# schematic_v2.net
KiCad netlist of a schematic drawn in EAGLE
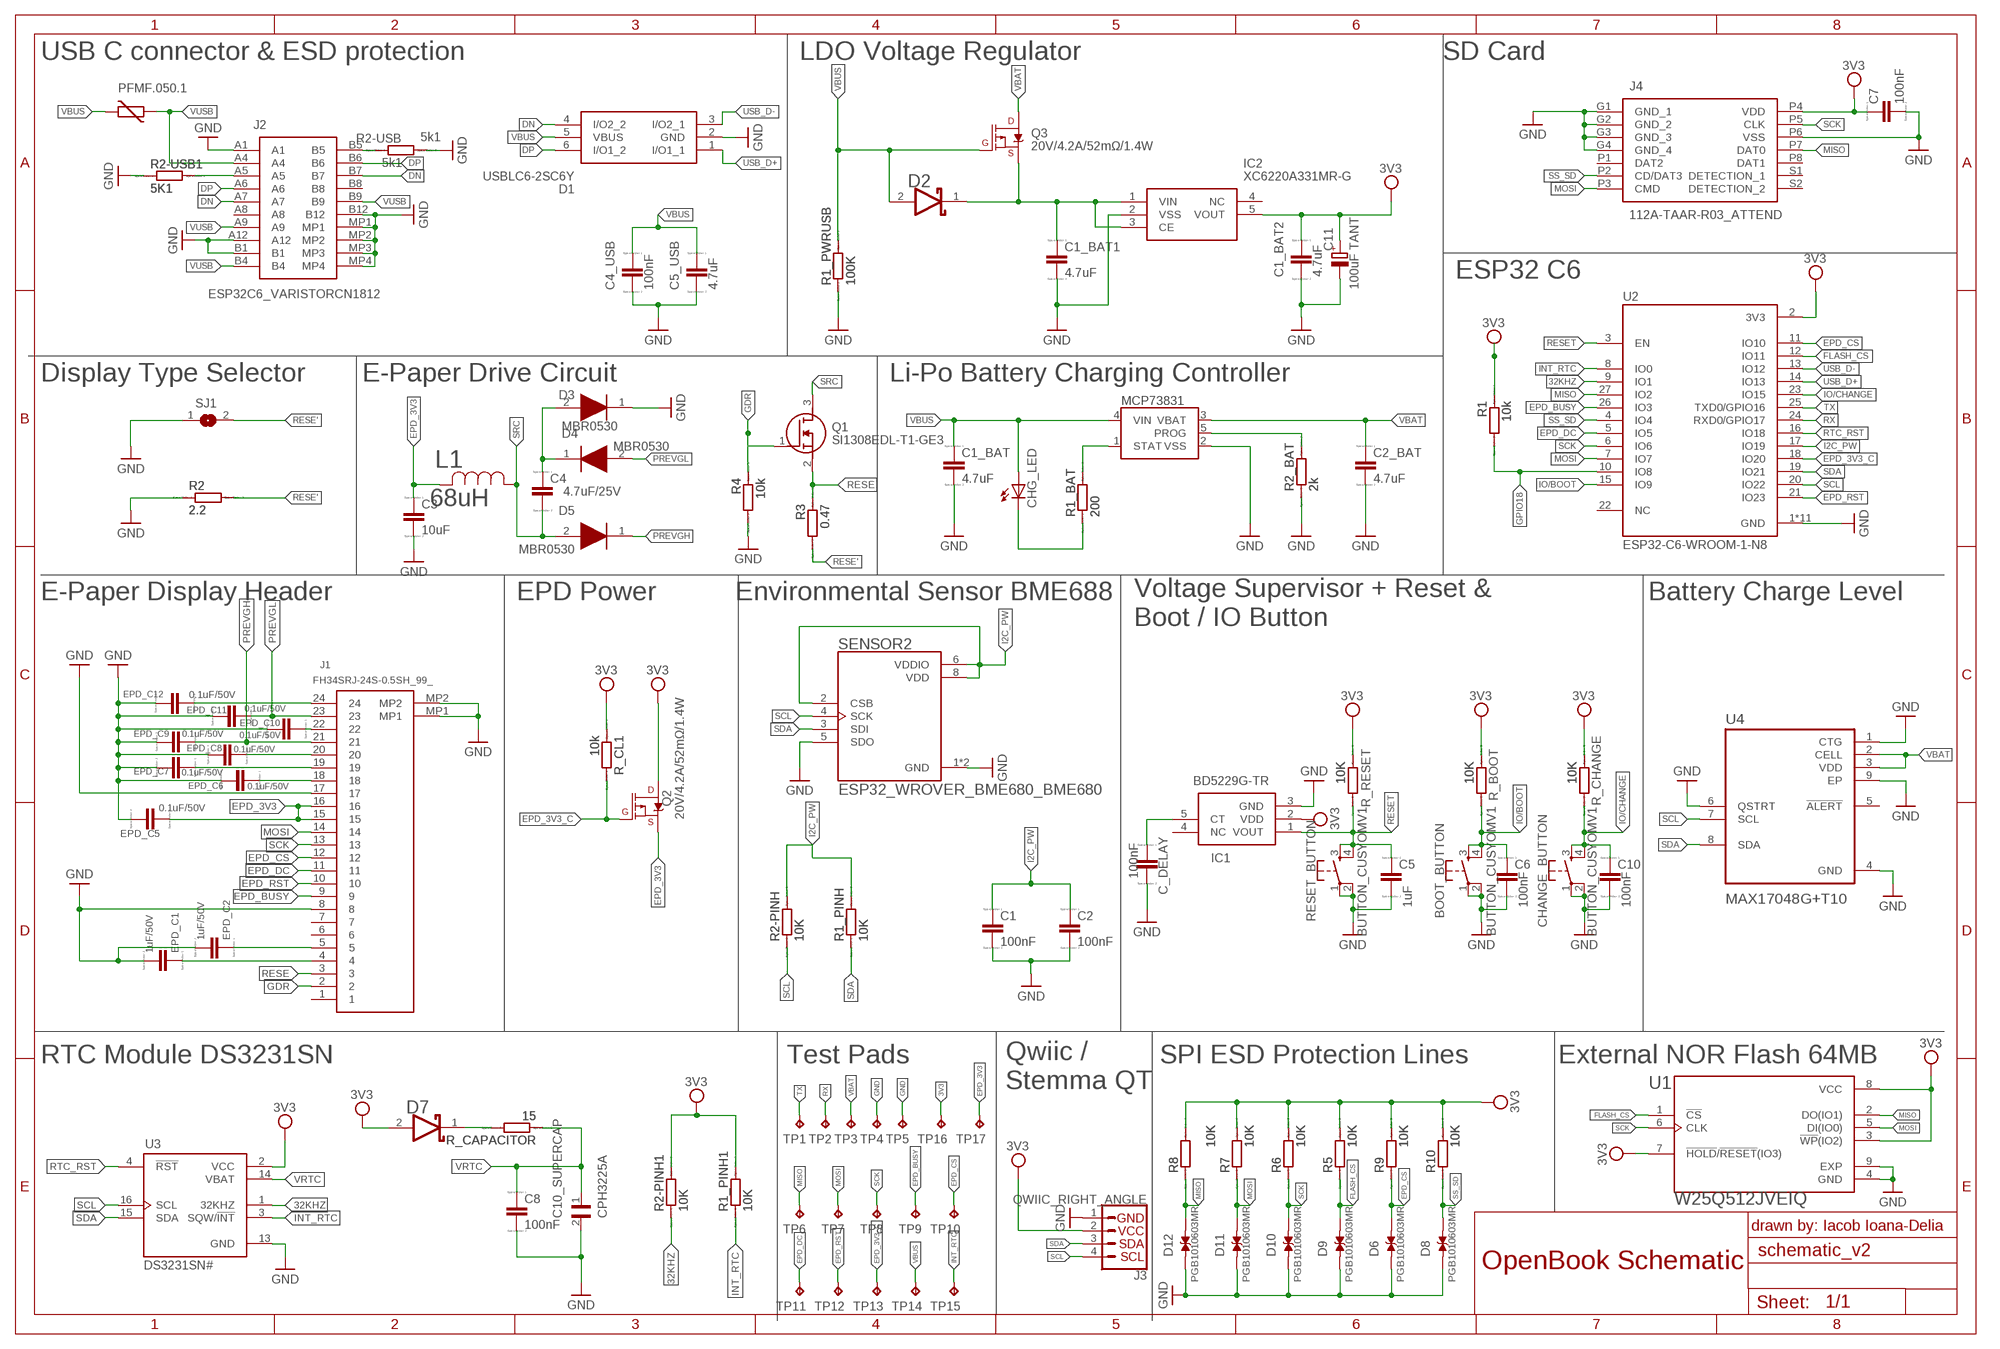
[diagram p0: schematic, sheet 1]

(export (version "E")
  (design (tool "Eeschema 10.0.6"))
  (components
    (comp (ref "BOOT_BUTTON")
      (value "BUTTON_CUSYOMV1")
      (footprint "eagle-import:MYBUTTON")
      (libsource (lib "eagle-import") (part "BUTTON_CUSYOMV1"))
    )
    (comp (ref "C1")
      (value "100nF")
      (footprint "eagle-import:ESP32_WROVER_EAGLE-LTSPICE_C0402")
      (libsource (lib "eagle-import") (part "ESP32_WROVER_EAGLE-LTSPICE_CC0402"))
    )
    (comp (ref "C1_BAT")
      (value "4.7uF")
      (footprint "eagle-import:ESP32_WROVER_EAGLE-LTSPICE_C0402")
      (libsource (lib "eagle-import") (part "ESP32_WROVER_EAGLE-LTSPICE_CC0402"))
    )
    (comp (ref "C1_BAT1")
      (value "4.7uF")
      (footprint "eagle-import:ESP32_WROVER_EAGLE-LTSPICE_C0402")
      (libsource (lib "eagle-import") (part "ESP32_WROVER_EAGLE-LTSPICE_CC0402"))
    )
    (comp (ref "C1_BAT2")
      (value "4.7uF")
      (footprint "eagle-import:ESP32_WROVER_EAGLE-LTSPICE_C0402")
      (libsource (lib "eagle-import") (part "ESP32_WROVER_EAGLE-LTSPICE_CC0402"))
    )
    (comp (ref "C2")
      (value "100nF")
      (footprint "eagle-import:ESP32_WROVER_EAGLE-LTSPICE_C0402")
      (libsource (lib "eagle-import") (part "ESP32_WROVER_EAGLE-LTSPICE_CC0402"))
    )
    (comp (ref "C2_BAT")
      (value "4.7uF")
      (footprint "eagle-import:ESP32_WROVER_EAGLE-LTSPICE_C0402")
      (libsource (lib "eagle-import") (part "ESP32_WROVER_EAGLE-LTSPICE_CC0402"))
    )
    (comp (ref "C3")
      (value "10uF")
      (footprint "eagle-import:ESP32_WROVER_EAGLE-LTSPICE_C0402")
      (libsource (lib "eagle-import") (part "ESP32_WROVER_EAGLE-LTSPICE_CC0402"))
    )
    (comp (ref "C4")
      (value "4.7uF/25V")
      (footprint "eagle-import:ESP32_WROVER_EAGLE-LTSPICE_C0402")
      (libsource (lib "eagle-import") (part "DeskAssistant_v19_v1_vf.EQLOxIDGRNyRrnCg3211Tg_ESP32_WROVER_EAGLE-LTSPICE_CC0402"))
    )
    (comp (ref "C4_USB")
      (value "100nF")
      (footprint "eagle-import:ESP32_WROVER_EAGLE-LTSPICE_C0402")
      (libsource (lib "eagle-import") (part "ESP32_WROVER_EAGLE-LTSPICE_CC0402"))
    )
    (comp (ref "C5")
      (value "1uF")
      (footprint "eagle-import:ESP32_WROVER_EAGLE-LTSPICE_C0402")
      (libsource (lib "eagle-import") (part "ESP32_WROVER_EAGLE-LTSPICE_CC0402"))
    )
    (comp (ref "C5_USB")
      (value "4.7uF")
      (footprint "eagle-import:ESP32_WROVER_EAGLE-LTSPICE_C0402")
      (libsource (lib "eagle-import") (part "ESP32_WROVER_EAGLE-LTSPICE_CC0402"))
    )
    (comp (ref "C6")
      (value "100nF")
      (footprint "eagle-import:ESP32_WROVER_EAGLE-LTSPICE_C0402")
      (libsource (lib "eagle-import") (part "ESP32_WROVER_EAGLE-LTSPICE_CC0402"))
    )
    (comp (ref "C7")
      (value "100nF")
      (footprint "eagle-import:ESP32_WROVER_EAGLE-LTSPICE_C0402")
      (libsource (lib "eagle-import") (part "ESP32_WROVER_EAGLE-LTSPICE_CC0402"))
    )
    (comp (ref "C8")
      (value "100nF")
      (footprint "eagle-import:ESP32_WROVER_EAGLE-LTSPICE_C0402")
      (libsource (lib "eagle-import") (part "ESP32_WROVER_EAGLE-LTSPICE_CC0402"))
    )
    (comp (ref "C10")
      (value "100nF")
      (footprint "eagle-import:ESP32_WROVER_EAGLE-LTSPICE_C0402")
      (libsource (lib "eagle-import") (part "ESP32_WROVER_EAGLE-LTSPICE_CC0402"))
    )
    (comp (ref "C10_SUPERCAP")
      (value "CPH3225A")
      (footprint "eagle-import:CAPCP3225X100N")
      (fields (field (name "MF") "Seiko Instruments"))
      (libsource (lib "eagle-import") (part "CPH3225A"))
    )
    (comp (ref "C11")
      (value "100uF TANT")
      (footprint "eagle-import:RCL_CT3528")
      (libsource (lib "eagle-import") (part "RCL_CPOL-EUCT3528"))
    )
    (comp (ref "CHANGE_BUTTON")
      (value "BUTTON_CUSYOMV1")
      (footprint "eagle-import:MYBUTTON")
      (libsource (lib "eagle-import") (part "BUTTON_CUSYOMV1"))
    )
    (comp (ref "CHG_LED")
      (value "ADAFRUIT_LEDCHIP-LED0603")
      (footprint "eagle-import:ADAFRUIT_CHIP-LED0603")
      (libsource (lib "eagle-import") (part "ADAFRUIT_LEDCHIP-LED0603"))
    )
    (comp (ref "C_DELAY")
      (value "100nF")
      (footprint "eagle-import:ESP32_WROVER_EAGLE-LTSPICE_C0402")
      (libsource (lib "eagle-import") (part "ESP32_WROVER_EAGLE-LTSPICE_CC0402"))
    )
    (comp (ref "D1")
      (value "USBLC6-2SC6Y")
      (footprint "eagle-import:SOT95P280X145-6N")
      (fields (field (name "MF") "STMicroelectronics"))
      (libsource (lib "eagle-import") (part "USBLC6-2SC6Y"))
    )
    (comp (ref "D2")
      (value "ESP32_WROVER_AVX---SD0805S020S1R0_AVX_SD0805S020S1R0_0_0AVX_SD0805S020S1R0_0_0")
      (footprint "eagle-import:ESP32_WROVER_AVX---SD0805S020S1R0_AVX_SD0805S020S1R0_0")
      (fields
        (field (name "DIGIKEY_PART_NUMBER") "478-7800-1-ND")
        (field (name "MF") "AVX")
        (field (name "MOUSER_PART_NUMBER") "581-SD0805S020S1R0")
      )
      (libsource (lib "eagle-import") (part "ESP32_WROVER_AVX---SD0805S020S1R0_AVX_SD0805S020S1R0_0_0AVX_SD0805S020S1R0_0_0"))
    )
    (comp (ref "D3")
      (value "MBR0530")
      (footprint "eagle-import:SOD3716X135N")
      (fields (field (name "MF") "ON Semiconductor"))
      (libsource (lib "eagle-import") (part "MBR0530"))
    )
    (comp (ref "D4")
      (value "MBR0530")
      (footprint "eagle-import:SOD3716X135N")
      (fields (field (name "MF") "ON Semiconductor"))
      (libsource (lib "eagle-import") (part "MBR0530"))
    )
    (comp (ref "D5")
      (value "MBR0530")
      (footprint "eagle-import:SOD3716X135N")
      (fields (field (name "MF") "ON Semiconductor"))
      (libsource (lib "eagle-import") (part "MBR0530"))
    )
    (comp (ref "D6")
      (value "PGB1010603MR")
      (footprint "eagle-import:DIOC1608X36N")
      (fields (field (name "MF") "Littelfuse Inc."))
      (libsource (lib "eagle-import") (part "PGB1010603MR"))
    )
    (comp (ref "D7")
      (value "ESP32_WROVER_AVX---SD0805S020S1R0_AVX_SD0805S020S1R0_0_0AVX_SD0805S020S1R0_0_0")
      (footprint "eagle-import:ESP32_WROVER_AVX---SD0805S020S1R0_AVX_SD0805S020S1R0_0")
      (fields
        (field (name "DIGIKEY_PART_NUMBER") "478-7800-1-ND")
        (field (name "MF") "AVX")
        (field (name "MOUSER_PART_NUMBER") "581-SD0805S020S1R0")
      )
      (libsource (lib "eagle-import") (part "ESP32_WROVER_AVX---SD0805S020S1R0_AVX_SD0805S020S1R0_0_0AVX_SD0805S020S1R0_0_0"))
    )
    (comp (ref "D8")
      (value "PGB1010603MR")
      (footprint "eagle-import:DIOC1608X36N")
      (fields (field (name "MF") "Littelfuse Inc."))
      (libsource (lib "eagle-import") (part "PGB1010603MR"))
    )
    (comp (ref "D9")
      (value "PGB1010603MR")
      (footprint "eagle-import:DIOC1608X36N")
      (fields (field (name "MF") "Littelfuse Inc."))
      (libsource (lib "eagle-import") (part "PGB1010603MR"))
    )
    (comp (ref "D10")
      (value "PGB1010603MR")
      (footprint "eagle-import:DIOC1608X36N")
      (fields (field (name "MF") "Littelfuse Inc."))
      (libsource (lib "eagle-import") (part "PGB1010603MR"))
    )
    (comp (ref "D11")
      (value "PGB1010603MR")
      (footprint "eagle-import:DIOC1608X36N")
      (fields (field (name "MF") "Littelfuse Inc."))
      (libsource (lib "eagle-import") (part "PGB1010603MR"))
    )
    (comp (ref "D12")
      (value "PGB1010603MR")
      (footprint "eagle-import:DIOC1608X36N")
      (fields (field (name "MF") "Littelfuse Inc."))
      (libsource (lib "eagle-import") (part "PGB1010603MR"))
    )
    (comp (ref "EPD_C1")
      (value "1uF/50V")
      (footprint "eagle-import:ESP32_WROVER_EAGLE-LTSPICE_C0402")
      (libsource (lib "eagle-import") (part "ESP32_WROVER_EAGLE-LTSPICE_CC0402"))
    )
    (comp (ref "EPD_C2")
      (value "1uF/50V")
      (footprint "eagle-import:ESP32_WROVER_EAGLE-LTSPICE_C0402")
      (libsource (lib "eagle-import") (part "ESP32_WROVER_EAGLE-LTSPICE_CC0402"))
    )
    (comp (ref "EPD_C5")
      (value "0.1uF/50V")
      (footprint "eagle-import:ESP32_WROVER_EAGLE-LTSPICE_C0402")
      (libsource (lib "eagle-import") (part "ESP32_WROVER_EAGLE-LTSPICE_CC0402"))
    )
    (comp (ref "EPD_C6")
      (value "0.1uF/50V")
      (footprint "eagle-import:ESP32_WROVER_EAGLE-LTSPICE_C0402")
      (libsource (lib "eagle-import") (part "ESP32_WROVER_EAGLE-LTSPICE_CC0402"))
    )
    (comp (ref "EPD_C7")
      (value "0.1uF/50V")
      (footprint "eagle-import:ESP32_WROVER_EAGLE-LTSPICE_C0402")
      (libsource (lib "eagle-import") (part "ESP32_WROVER_EAGLE-LTSPICE_CC0402"))
    )
    (comp (ref "EPD_C8")
      (value "0.1uF/50V")
      (footprint "eagle-import:ESP32_WROVER_EAGLE-LTSPICE_C0402")
      (libsource (lib "eagle-import") (part "ESP32_WROVER_EAGLE-LTSPICE_CC0402"))
    )
    (comp (ref "EPD_C9")
      (value "0.1uF/50V")
      (footprint "eagle-import:ESP32_WROVER_EAGLE-LTSPICE_C0402")
      (libsource (lib "eagle-import") (part "ESP32_WROVER_EAGLE-LTSPICE_CC0402"))
    )
    (comp (ref "EPD_C10")
      (value "0.1uF/50V")
      (footprint "eagle-import:ESP32_WROVER_EAGLE-LTSPICE_C0402")
      (libsource (lib "eagle-import") (part "ESP32_WROVER_EAGLE-LTSPICE_CC0402"))
    )
    (comp (ref "EPD_C11")
      (value "0.1uF/50V")
      (footprint "eagle-import:ESP32_WROVER_EAGLE-LTSPICE_C0402")
      (libsource (lib "eagle-import") (part "ESP32_WROVER_EAGLE-LTSPICE_CC0402"))
    )
    (comp (ref "EPD_C12")
      (value "0.1uF/50V")
      (footprint "eagle-import:ESP32_WROVER_EAGLE-LTSPICE_C0402")
      (libsource (lib "eagle-import") (part "ESP32_WROVER_EAGLE-LTSPICE_CC0402"))
    )
    (comp (ref "IC1")
      (value "BD5229G-TR")
      (footprint "eagle-import:SOT95P280X125-5N")
      (fields (field (name "MOUSER_PART_NUMBER") "755-BD5229G-TR"))
      (libsource (lib "eagle-import") (part "BD5229G-TR"))
    )
    (comp (ref "IC2")
      (value "XC6220A331MR-G")
      (footprint "eagle-import:SOT95P280X120-5N")
      (fields (field (name "MOUSER_PART_NUMBER") "865-XC6220A331MR-G"))
      (libsource (lib "eagle-import") (part "XC6220A331MR-G"))
    )
    (comp (ref "J1")
      (value "FH34SRJ-24S-0.5SH_99_")
      (footprint "eagle-import:FH34SRJ24S05SH99")
      (fields
        (field (name "MANUFACTURER_PART_NUMBER") "FH34SRJ-24S-0.5SH(99)")
        (field (name "MOUSER_PART_NUMBER") "798-FH34SRJ24S05SH99")
      )
      (libsource (lib "eagle-import") (part "FH34SRJ-24S-0.5SH_99_"))
    )
    (comp (ref "J2")
      (value "SAMACSYS_PARTS_USB4110-GF-A")
      (footprint "eagle-import:SAMACSYS_PARTS_USB4110GFA")
      (fields
        (field (name "MANUFACTURER_PART_NUMBER") "USB4110-GF-A")
        (field (name "MOUSER_PART_NUMBER") "640-USB4110-GF-A")
      )
      (libsource (lib "eagle-import") (part "SAMACSYS_PARTS_USB4110-GF-A"))
    )
    (comp (ref "J3")
      (value "QWIIC_RIGHT_ANGLE")
      (footprint "eagle-import:JST04_1MM_RA")
      (libsource (lib "eagle-import") (part "QWIIC_CONNECTORJS-1MM"))
    )
    (comp (ref "J4")
      (value "112A-TAAR-R03_ATTEND")
      (footprint "eagle-import:112ATAARR03ATTEND")
      (fields (field (name "MANUFACTURER_PART_NUMBER") "112A-TAAR-R03 ATTEND"))
      (libsource (lib "eagle-import") (part "112A-TAAR-R03_ATTEND"))
    )
    (comp (ref "L1")
      (value "68uH")
      (footprint "eagle-import:IND_4828-WE-TPC_WRE")
      (fields
        (field (name "MANUFACTURER_PART_NUMBER") "744043680")
        (field (name "COPYRIGHT") "Copyright (C) 2024 Ultra Librarian. All rights reserved.")
      )
      (libsource (lib "eagle-import") (part "744043680IND_4828-WE-TPC_WRE"))
    )
    (comp (ref "MCP73831")
      (value "ESP32_WROVER_SPARKFUN-IC-POWER_MCP73831")
      (footprint "eagle-import:ESP32_WROVER_SPARKFUN-IC-POWER_SOT23-5")
      (libsource (lib "eagle-import") (part "ESP32_WROVER_SPARKFUN-IC-POWER_MCP73831"))
    )
    (comp (ref "PFMF.050.1")
      (value "ESP32C6_VARISTORCN1812")
      (footprint "eagle-import:ESP32C6_VARISTOR_CT_CN1812")
      (libsource (lib "eagle-import") (part "ESP32C6_VARISTORCN1812"))
    )
    (comp (ref "Q1")
      (value "SI1308EDL-T1-GE3")
      (footprint "eagle-import:SOT65P210X110-3N")
      (fields (field (name "MF") "Vishay Siliconix"))
      (libsource (lib "eagle-import") (part "SI1308EDL-T1-GE3"))
    )
    (comp (ref "Q2")
      (value "20V/4.2A/52mΩ/1.4W")
      (footprint "eagle-import:ESP32_WROVER_SPARKFUN-DISCRETESEMI_SOT23-3")
      (libsource (lib "eagle-import") (part "ESP32_WROVER_SPARKFUN-DISCRETESEMI_MOSFET_PCH-DMG2305UX-7"))
    )
    (comp (ref "Q3")
      (value "20V/4.2A/52mΩ/1.4W")
      (footprint "eagle-import:ESP32_WROVER_SPARKFUN-DISCRETESEMI_SOT23-3")
      (libsource (lib "eagle-import") (part "ESP32_WROVER_SPARKFUN-DISCRETESEMI_MOSFET_PCH-DMG2305UX-7"))
    )
    (comp (ref "R1")
      (value "10k")
      (footprint "eagle-import:ESP32_WROVER_EAGLE-LTSPICE_R0402")
      (libsource (lib "eagle-import") (part "DeskAssistant_v19_v1_vf.EQLOxIDGRNyRrnCg3211Tg_ESP32_WROVER_EAGLE-LTSPICE_RR0402"))
    )
    (comp (ref "R1_BAT")
      (value "200")
      (footprint "eagle-import:ESP32_WROVER_EAGLE-LTSPICE_R0402")
      (libsource (lib "eagle-import") (part "DeskAssistant_v19_v1_vf.EQLOxIDGRNyRrnCg3211Tg_ESP32_WROVER_EAGLE-LTSPICE_RR0402"))
    )
    (comp (ref "R1_PINH")
      (value "10K")
      (footprint "eagle-import:ESP32_WROVER_EAGLE-LTSPICE_R0402")
      (libsource (lib "eagle-import") (part "DeskAssistant_v19_v1_vf.EQLOxIDGRNyRrnCg3211Tg_ESP32_WROVER_EAGLE-LTSPICE_RR0402"))
    )
    (comp (ref "R1_PINH1")
      (value "10K")
      (footprint "eagle-import:ESP32_WROVER_EAGLE-LTSPICE_R0402")
      (libsource (lib "eagle-import") (part "DeskAssistant_v19_v1_vf.EQLOxIDGRNyRrnCg3211Tg_ESP32_WROVER_EAGLE-LTSPICE_RR0402"))
    )
    (comp (ref "R1_PWRUSB")
      (value "100K")
      (footprint "eagle-import:ESP32_WROVER_EAGLE-LTSPICE_R0402")
      (libsource (lib "eagle-import") (part "DeskAssistant_v19_v1_vf.EQLOxIDGRNyRrnCg3211Tg_ESP32_WROVER_EAGLE-LTSPICE_RR0402"))
    )
    (comp (ref "R2")
      (value "2.2")
      (footprint "eagle-import:ESP32_WROVER_EAGLE-LTSPICE_R0402")
      (libsource (lib "eagle-import") (part "DeskAssistant_v19_v1_vf.EQLOxIDGRNyRrnCg3211Tg_ESP32_WROVER_EAGLE-LTSPICE_RR0402"))
    )
    (comp (ref "R2-PINH")
      (value "10K")
      (footprint "eagle-import:ESP32_WROVER_EAGLE-LTSPICE_R0402")
      (libsource (lib "eagle-import") (part "DeskAssistant_v19_v1_vf.EQLOxIDGRNyRrnCg3211Tg_ESP32_WROVER_EAGLE-LTSPICE_RR0402"))
    )
    (comp (ref "R2-PINH1")
      (value "10K")
      (footprint "eagle-import:ESP32_WROVER_EAGLE-LTSPICE_R0402")
      (libsource (lib "eagle-import") (part "DeskAssistant_v19_v1_vf.EQLOxIDGRNyRrnCg3211Tg_ESP32_WROVER_EAGLE-LTSPICE_RR0402"))
    )
    (comp (ref "R2-USB")
      (value "5k1")
      (footprint "eagle-import:ESP32_WROVER_EAGLE-LTSPICE_R0402")
      (libsource (lib "eagle-import") (part "DeskAssistant_v19_v1_vf.EQLOxIDGRNyRrnCg3211Tg_ESP32_WROVER_EAGLE-LTSPICE_RR0402"))
    )
    (comp (ref "R2-USB1")
      (value "5K1")
      (footprint "eagle-import:ESP32_WROVER_EAGLE-LTSPICE_R0402")
      (libsource (lib "eagle-import") (part "DeskAssistant_v19_v1_vf.EQLOxIDGRNyRrnCg3211Tg_ESP32_WROVER_EAGLE-LTSPICE_RR0402"))
    )
    (comp (ref "R2_BAT")
      (value "2k")
      (footprint "eagle-import:ESP32_WROVER_EAGLE-LTSPICE_R0402")
      (libsource (lib "eagle-import") (part "DeskAssistant_v19_v1_vf.EQLOxIDGRNyRrnCg3211Tg_ESP32_WROVER_EAGLE-LTSPICE_RR0402"))
    )
    (comp (ref "R3")
      (value "0.47")
      (footprint "eagle-import:ESP32_WROVER_EAGLE-LTSPICE_R0402")
      (libsource (lib "eagle-import") (part "ESP32_WROVER_EAGLE-LTSPICE_RR0402"))
    )
    (comp (ref "R4")
      (value "10k")
      (footprint "eagle-import:ESP32_WROVER_EAGLE-LTSPICE_R0402")
      (libsource (lib "eagle-import") (part "ESP32_WROVER_EAGLE-LTSPICE_RR0402"))
    )
    (comp (ref "R5")
      (value "10K")
      (footprint "eagle-import:ESP32_WROVER_EAGLE-LTSPICE_R0402")
      (libsource (lib "eagle-import") (part "DeskAssistant_v19_v1_vf.EQLOxIDGRNyRrnCg3211Tg_ESP32_WROVER_EAGLE-LTSPICE_RR0402"))
    )
    (comp (ref "R6")
      (value "10K")
      (footprint "eagle-import:ESP32_WROVER_EAGLE-LTSPICE_R0402")
      (libsource (lib "eagle-import") (part "DeskAssistant_v19_v1_vf.EQLOxIDGRNyRrnCg3211Tg_ESP32_WROVER_EAGLE-LTSPICE_RR0402"))
    )
    (comp (ref "R7")
      (value "10K")
      (footprint "eagle-import:ESP32_WROVER_EAGLE-LTSPICE_R0402")
      (libsource (lib "eagle-import") (part "DeskAssistant_v19_v1_vf.EQLOxIDGRNyRrnCg3211Tg_ESP32_WROVER_EAGLE-LTSPICE_RR0402"))
    )
    (comp (ref "R8")
      (value "10K")
      (footprint "eagle-import:ESP32_WROVER_EAGLE-LTSPICE_R0402")
      (libsource (lib "eagle-import") (part "DeskAssistant_v19_v1_vf.EQLOxIDGRNyRrnCg3211Tg_ESP32_WROVER_EAGLE-LTSPICE_RR0402"))
    )
    (comp (ref "R9")
      (value "10K")
      (footprint "eagle-import:ESP32_WROVER_EAGLE-LTSPICE_R0402")
      (libsource (lib "eagle-import") (part "DeskAssistant_v19_v1_vf.EQLOxIDGRNyRrnCg3211Tg_ESP32_WROVER_EAGLE-LTSPICE_RR0402"))
    )
    (comp (ref "R10")
      (value "10K")
      (footprint "eagle-import:ESP32_WROVER_EAGLE-LTSPICE_R0402")
      (libsource (lib "eagle-import") (part "DeskAssistant_v19_v1_vf.EQLOxIDGRNyRrnCg3211Tg_ESP32_WROVER_EAGLE-LTSPICE_RR0402"))
    )
    (comp (ref "RESET_BUTTON")
      (value "BUTTON_CUSYOMV1")
      (footprint "eagle-import:MYBUTTON")
      (libsource (lib "eagle-import") (part "BUTTON_CUSYOMV1"))
    )
    (comp (ref "R_BOOT")
      (value "10K")
      (footprint "eagle-import:ESP32_WROVER_EAGLE-LTSPICE_R0402")
      (libsource (lib "eagle-import") (part "DeskAssistant_v19_v1_vf.EQLOxIDGRNyRrnCg3211Tg_ESP32_WROVER_EAGLE-LTSPICE_RR0402"))
    )
    (comp (ref "R_CAPACITOR")
      (value "15")
      (footprint "eagle-import:ESP32_WROVER_EAGLE-LTSPICE_R0402")
      (libsource (lib "eagle-import") (part "DeskAssistant_v19_v1_vf.EQLOxIDGRNyRrnCg3211Tg_ESP32_WROVER_EAGLE-LTSPICE_RR0402"))
    )
    (comp (ref "R_CHANGE")
      (value "10K")
      (footprint "eagle-import:ESP32_WROVER_EAGLE-LTSPICE_R0402")
      (libsource (lib "eagle-import") (part "DeskAssistant_v19_v1_vf.EQLOxIDGRNyRrnCg3211Tg_ESP32_WROVER_EAGLE-LTSPICE_RR0402"))
    )
    (comp (ref "R_CL1")
      (value "10k")
      (footprint "eagle-import:ESP32_WROVER_EAGLE-LTSPICE_R0402")
      (libsource (lib "eagle-import") (part "DeskAssistant_v19_v1_vf.EQLOxIDGRNyRrnCg3211Tg_ESP32_WROVER_EAGLE-LTSPICE_RR0402"))
    )
    (comp (ref "R_RESET")
      (value "10K")
      (footprint "eagle-import:ESP32_WROVER_EAGLE-LTSPICE_R0402")
      (libsource (lib "eagle-import") (part "DeskAssistant_v19_v1_vf.EQLOxIDGRNyRrnCg3211Tg_ESP32_WROVER_EAGLE-LTSPICE_RR0402"))
    )
    (comp (ref "SENSOR2")
      (value "ESP32_WROVER_BME680_BME680")
      (footprint "eagle-import:ESP32_WROVER_BME680_PSON80P300X300X100-8N")
      (fields (field (name "MF") "Bosch Sensortec") (field (name "MP") "BME680"))
      (libsource (lib "eagle-import") (part "ESP32_WROVER_BME680_BME680"))
    )
    (comp (ref "SJ1") (value "SJ") (footprint "eagle-import:SJ") (libsource (lib "eagle-import") (part "SJ")))
    (comp (ref "TP1")
      (value "TPTP20R")
      (footprint "eagle-import:TP20R")
      (libsource (lib "eagle-import") (part "TPTP20R"))
    )
    (comp (ref "TP2")
      (value "TPTP20R")
      (footprint "eagle-import:TP20R")
      (libsource (lib "eagle-import") (part "TPTP20R"))
    )
    (comp (ref "TP3")
      (value "TPTP20R")
      (footprint "eagle-import:TP20R")
      (libsource (lib "eagle-import") (part "TPTP20R"))
    )
    (comp (ref "TP4")
      (value "TPTP20R")
      (footprint "eagle-import:TP20R")
      (libsource (lib "eagle-import") (part "TPTP20R"))
    )
    (comp (ref "TP5")
      (value "TPTP20R")
      (footprint "eagle-import:TP20R")
      (libsource (lib "eagle-import") (part "TPTP20R"))
    )
    (comp (ref "TP6")
      (value "TPTP20R")
      (footprint "eagle-import:TP20R")
      (libsource (lib "eagle-import") (part "TPTP20R"))
    )
    (comp (ref "TP7")
      (value "TPTP20R")
      (footprint "eagle-import:TP20R")
      (libsource (lib "eagle-import") (part "TPTP20R"))
    )
    (comp (ref "TP8")
      (value "TPTP20R")
      (footprint "eagle-import:TP20R")
      (libsource (lib "eagle-import") (part "TPTP20R"))
    )
    (comp (ref "TP9")
      (value "TPTP20R")
      (footprint "eagle-import:TP20R")
      (libsource (lib "eagle-import") (part "TPTP20R"))
    )
    (comp (ref "TP10")
      (value "TPTP20R")
      (footprint "eagle-import:TP20R")
      (libsource (lib "eagle-import") (part "TPTP20R"))
    )
    (comp (ref "TP11")
      (value "TPTP20R")
      (footprint "eagle-import:TP20R")
      (libsource (lib "eagle-import") (part "TPTP20R"))
    )
    (comp (ref "TP12")
      (value "TPTP20R")
      (footprint "eagle-import:TP20R")
      (libsource (lib "eagle-import") (part "TPTP20R"))
    )
    (comp (ref "TP13")
      (value "TPTP20R")
      (footprint "eagle-import:TP20R")
      (libsource (lib "eagle-import") (part "TPTP20R"))
    )
    (comp (ref "TP14")
      (value "TPTP20R")
      (footprint "eagle-import:TP20R")
      (libsource (lib "eagle-import") (part "TPTP20R"))
    )
    (comp (ref "TP15")
      (value "TPTP20R")
      (footprint "eagle-import:TP20R")
      (libsource (lib "eagle-import") (part "TPTP20R"))
    )
    (comp (ref "TP16")
      (value "TPTP20R")
      (footprint "eagle-import:TP20R")
      (libsource (lib "eagle-import") (part "TPTP20R"))
    )
    (comp (ref "TP17")
      (value "TPTP20R")
      (footprint "eagle-import:TP20R")
      (libsource (lib "eagle-import") (part "TPTP20R"))
    )
    (comp (ref "U1")
      (value "W25Q512JVEIQ")
      (footprint "eagle-import:SON127P600X800X80-9N")
      (fields (field (name "MF") "Winbond Electronics"))
      (libsource (lib "eagle-import") (part "W25Q512JVEIQ"))
    )
    (comp (ref "U2")
      (value "ESP32-C6-WROOM-1-N8")
      (footprint "eagle-import:XCVR_ESP32-C6-WROOM-1-N8")
      (fields (field (name "MF") "Espressif Systems"))
      (libsource (lib "eagle-import") (part "ESP32-C6-WROOM-1-N8"))
    )
    (comp (ref "U3")
      (value "DS3231SN#")
      (footprint "eagle-import:SOIC127P1032X265-16N")
      (fields (field (name "MF") "Analog Devices"))
      (libsource (lib "eagle-import") (part "DS3231SN#"))
    )
    (comp (ref "U4")
      (value "MAX17048G+T10")
      (footprint "eagle-import:SON50P200X200X80-9N")
      (fields (field (name "MF") "Analog Devices"))
      (libsource (lib "eagle-import") (part "MAX17048G+T10"))
    )
  )
  (nets
    (net (code "1") (name "3V3") (class "Default")
      (node (ref "C11") (pin "+") (pinfunction "+_+") (pintype "passive"))
      (node (ref "C1_BAT2") (pin "1") (pinfunction "1_1") (pintype "passive"))
      (node (ref "C7") (pin "1") (pinfunction "1_1") (pintype "passive"))
      (node (ref "D7") (pin "2") (pinfunction "ANODE_2") (pintype "bidirectional"))
      (node (ref "IC1") (pin "2") (pinfunction "VDD_2") (pintype "bidirectional"))
      (node (ref "IC2") (pin "5") (pinfunction "VOUT_5") (pintype "bidirectional"))
      (node (ref "J3") (pin "2") (pinfunction "2_2") (pintype "power_in"))
      (node (ref "J4") (pin "P4") (pinfunction "VDD_P4") (pintype "bidirectional"))
      (node (ref "Q2") (pin "3") (pinfunction "D_3") (pintype "bidirectional"))
      (node (ref "R1") (pin "1") (pinfunction "1_1") (pintype "passive"))
      (node (ref "R10") (pin "2") (pinfunction "2_2") (pintype "passive"))
      (node (ref "R1_PINH1") (pin "2") (pinfunction "2_2") (pintype "passive"))
      (node (ref "R2-PINH1") (pin "2") (pinfunction "2_2") (pintype "passive"))
      (node (ref "R5") (pin "2") (pinfunction "2_2") (pintype "passive"))
      (node (ref "R6") (pin "2") (pinfunction "2_2") (pintype "passive"))
      (node (ref "R7") (pin "2") (pinfunction "2_2") (pintype "passive"))
      (node (ref "R8") (pin "2") (pinfunction "2_2") (pintype "passive"))
      (node (ref "R9") (pin "2") (pinfunction "2_2") (pintype "passive"))
      (node (ref "R_BOOT") (pin "1") (pinfunction "1_1") (pintype "passive"))
      (node (ref "R_CHANGE") (pin "1") (pinfunction "1_1") (pintype "passive"))
      (node (ref "R_CL1") (pin "1") (pinfunction "1_1") (pintype "passive"))
      (node (ref "R_RESET") (pin "1") (pinfunction "1_1") (pintype "passive"))
      (node (ref "TP16") (pin "TP") (pinfunction "TP_TP") (pintype "input"))
      (node (ref "U1") (pin "3") (pinfunction "~{WP}(IO2)_3") (pintype "bidirectional"))
      (node (ref "U1") (pin "7") (pinfunction "~{HOLD}/~{RESET}(IO3)_7") (pintype "bidirectional"))
      (node (ref "U1") (pin "8") (pinfunction "VCC_8") (pintype "power_in"))
      (node (ref "U2") (pin "2") (pinfunction "3V3_2") (pintype "power_in"))
      (node (ref "U3") (pin "2") (pinfunction "VCC_2") (pintype "power_in"))
    )
    (net (code "2") (name "32KHZ") (class "Default")
      (node (ref "R2-PINH1") (pin "1") (pinfunction "1_1") (pintype "passive"))
      (node (ref "U2") (pin "9") (pinfunction "IO1_9") (pintype "bidirectional"))
      (node (ref "U3") (pin "1") (pinfunction "32KHZ_1") (pintype "output"))
    )
    (net (code "3") (name "DN") (class "Default")
      (node (ref "D1") (pin "4") (pinfunction "I/O2_2_4") (pintype "bidirectional"))
      (node (ref "J2") (pin "A7") (pinfunction "A7_A7") (pintype "bidirectional"))
      (node (ref "J2") (pin "B7") (pinfunction "B7_B7") (pintype "bidirectional"))
    )
    (net (code "4") (name "DP") (class "Default")
      (node (ref "D1") (pin "6") (pinfunction "I/O1_2_6") (pintype "bidirectional"))
      (node (ref "J2") (pin "A6") (pinfunction "A6_A6") (pintype "bidirectional"))
      (node (ref "J2") (pin "B6") (pinfunction "B6_B6") (pintype "bidirectional"))
    )
    (net (code "5") (name "EPD_3V3") (class "Default")
      (node (ref "C3") (pin "1") (pinfunction "1_1") (pintype "passive"))
      (node (ref "EPD_C5") (pin "1") (pinfunction "1_1") (pintype "passive"))
      (node (ref "J1") (pin "15") (pinfunction "15_15") (pintype "bidirectional"))
      (node (ref "J1") (pin "16") (pinfunction "16_16") (pintype "bidirectional"))
      (node (ref "L1") (pin "2") (pinfunction "2_2") (pintype "passive"))
      (node (ref "Q2") (pin "2") (pinfunction "S_2") (pintype "bidirectional"))
      (node (ref "TP17") (pin "TP") (pinfunction "TP_TP") (pintype "input"))
    )
    (net (code "6") (name "EPD_3V3_C") (class "Default")
      (node (ref "Q2") (pin "1") (pinfunction "G_1") (pintype "bidirectional"))
      (node (ref "R_CL1") (pin "2") (pinfunction "2_2") (pintype "passive"))
      (node (ref "TP13") (pin "TP") (pinfunction "TP_TP") (pintype "input"))
      (node (ref "U2") (pin "18") (pinfunction "IO20_18") (pintype "bidirectional"))
    )
    (net (code "7") (name "EPD_BUSY") (class "Default")
      (node (ref "J1") (pin "9") (pinfunction "9_9") (pintype "bidirectional"))
      (node (ref "TP9") (pin "TP") (pinfunction "TP_TP") (pintype "input"))
      (node (ref "U2") (pin "26") (pinfunction "IO3_26") (pintype "bidirectional"))
    )
    (net (code "8") (name "EPD_CS") (class "Default")
      (node (ref "D6") (pin "2") (pinfunction "2_2") (pintype "passive"))
      (node (ref "J1") (pin "12") (pinfunction "12_12") (pintype "bidirectional"))
      (node (ref "R9") (pin "1") (pinfunction "1_1") (pintype "passive"))
      (node (ref "TP10") (pin "TP") (pinfunction "TP_TP") (pintype "input"))
      (node (ref "U2") (pin "11") (pinfunction "IO10_11") (pintype "bidirectional"))
    )
    (net (code "9") (name "EPD_DC") (class "Default")
      (node (ref "J1") (pin "11") (pinfunction "11_11") (pintype "bidirectional"))
      (node (ref "TP11") (pin "TP") (pinfunction "TP_TP") (pintype "input"))
      (node (ref "U2") (pin "5") (pinfunction "IO5_5") (pintype "bidirectional"))
    )
    (net (code "10") (name "EPD_RST") (class "Default")
      (node (ref "J1") (pin "10") (pinfunction "10_10") (pintype "bidirectional"))
      (node (ref "TP12") (pin "TP") (pinfunction "TP_TP") (pintype "input"))
      (node (ref "U2") (pin "21") (pinfunction "IO23_21") (pintype "bidirectional"))
    )
    (net (code "11") (name "FLASH_CS") (class "Default")
      (node (ref "D9") (pin "2") (pinfunction "2_2") (pintype "passive"))
      (node (ref "R5") (pin "1") (pinfunction "1_1") (pintype "passive"))
      (node (ref "U1") (pin "1") (pinfunction "~{CS}_1") (pintype "input"))
      (node (ref "U2") (pin "12") (pinfunction "IO11_12") (pintype "bidirectional"))
    )
    (net (code "12") (name "GDR") (class "Default")
      (node (ref "J1") (pin "2") (pinfunction "2_2") (pintype "bidirectional"))
      (node (ref "Q1") (pin "1") (pinfunction "G_1") (pintype "bidirectional"))
      (node (ref "R4") (pin "1") (pinfunction "1_1") (pintype "passive"))
    )
    (net (code "13") (name "GND") (class "Default")
      (node (ref "BOOT_BUTTON") (pin "1") (pinfunction "1_1") (pintype "passive"))
      (node (ref "BOOT_BUTTON") (pin "2") (pinfunction "2_2") (pintype "passive"))
      (node (ref "C1") (pin "2") (pinfunction "2_2") (pintype "passive"))
      (node (ref "C10") (pin "2") (pinfunction "2_2") (pintype "passive"))
      (node (ref "C10_SUPERCAP") (pin "2") (pinfunction "2_2") (pintype "passive"))
      (node (ref "C11") (pin "-") (pinfunction "-_-") (pintype "passive"))
      (node (ref "C1_BAT") (pin "2") (pinfunction "2_2") (pintype "passive"))
      (node (ref "C1_BAT1") (pin "2") (pinfunction "2_2") (pintype "passive"))
      (node (ref "C1_BAT2") (pin "2") (pinfunction "2_2") (pintype "passive"))
      (node (ref "C2") (pin "2") (pinfunction "2_2") (pintype "passive"))
      (node (ref "C2_BAT") (pin "2") (pinfunction "2_2") (pintype "passive"))
      (node (ref "C3") (pin "2") (pinfunction "2_2") (pintype "passive"))
      (node (ref "C4_USB") (pin "2") (pinfunction "2_2") (pintype "passive"))
      (node (ref "C5") (pin "2") (pinfunction "2_2") (pintype "passive"))
      (node (ref "C5_USB") (pin "2") (pinfunction "2_2") (pintype "passive"))
      (node (ref "C6") (pin "2") (pinfunction "2_2") (pintype "passive"))
      (node (ref "C7") (pin "2") (pinfunction "2_2") (pintype "passive"))
      (node (ref "C8") (pin "2") (pinfunction "2_2") (pintype "passive"))
      (node (ref "CHANGE_BUTTON") (pin "1") (pinfunction "1_1") (pintype "passive"))
      (node (ref "CHANGE_BUTTON") (pin "2") (pinfunction "2_2") (pintype "passive"))
      (node (ref "C_DELAY") (pin "2") (pinfunction "2_2") (pintype "passive"))
      (node (ref "D1") (pin "2") (pinfunction "GND_2") (pintype "bidirectional"))
      (node (ref "D10") (pin "1") (pinfunction "1_1") (pintype "passive"))
      (node (ref "D11") (pin "1") (pinfunction "1_1") (pintype "passive"))
      (node (ref "D12") (pin "1") (pinfunction "1_1") (pintype "passive"))
      (node (ref "D3") (pin "1") (pinfunction "K_1") (pintype "bidirectional"))
      (node (ref "D6") (pin "1") (pinfunction "1_1") (pintype "passive"))
      (node (ref "D8") (pin "1") (pinfunction "1_1") (pintype "passive"))
      (node (ref "D9") (pin "1") (pinfunction "1_1") (pintype "passive"))
      (node (ref "EPD_C1") (pin "2") (pinfunction "2_2") (pintype "passive"))
      (node (ref "EPD_C10") (pin "2") (pinfunction "2_2") (pintype "passive"))
      (node (ref "EPD_C11") (pin "2") (pinfunction "2_2") (pintype "passive"))
      (node (ref "EPD_C12") (pin "2") (pinfunction "2_2") (pintype "passive"))
      (node (ref "EPD_C2") (pin "2") (pinfunction "2_2") (pintype "passive"))
      (node (ref "EPD_C5") (pin "2") (pinfunction "2_2") (pintype "passive"))
      (node (ref "EPD_C6") (pin "2") (pinfunction "2_2") (pintype "passive"))
      (node (ref "EPD_C7") (pin "2") (pinfunction "2_2") (pintype "passive"))
      (node (ref "EPD_C8") (pin "2") (pinfunction "2_2") (pintype "passive"))
      (node (ref "EPD_C9") (pin "2") (pinfunction "2_2") (pintype "passive"))
      (node (ref "IC1") (pin "3") (pinfunction "GND_3") (pintype "bidirectional"))
      (node (ref "IC2") (pin "2") (pinfunction "VSS_2") (pintype "bidirectional"))
      (node (ref "J1") (pin "17") (pinfunction "17_17") (pintype "bidirectional"))
      (node (ref "J1") (pin "8") (pinfunction "8_8") (pintype "bidirectional"))
      (node (ref "J1") (pin "MP1") (pinfunction "MP1_MP1") (pintype "bidirectional"))
      (node (ref "J1") (pin "MP2") (pinfunction "MP2_MP2") (pintype "bidirectional"))
      (node (ref "J2") (pin "A1") (pinfunction "A1_A1") (pintype "bidirectional"))
      (node (ref "J2") (pin "A12") (pinfunction "A12_A12") (pintype "bidirectional"))
      (node (ref "J2") (pin "B1") (pinfunction "B1_B1") (pintype "bidirectional"))
      (node (ref "J2") (pin "B12") (pinfunction "B12_B12") (pintype "bidirectional"))
      (node (ref "J2") (pin "MP1") (pinfunction "MP1_MP1") (pintype "bidirectional"))
      (node (ref "J2") (pin "MP2") (pinfunction "MP2_MP2") (pintype "bidirectional"))
      (node (ref "J2") (pin "MP3") (pinfunction "MP3_MP3") (pintype "bidirectional"))
      (node (ref "J2") (pin "MP4") (pinfunction "MP4_MP4") (pintype "bidirectional"))
      (node (ref "J3") (pin "1") (pinfunction "1_1") (pintype "power_in"))
      (node (ref "J4") (pin "G1") (pinfunction "GND_1_G1") (pintype "bidirectional"))
      (node (ref "J4") (pin "G2") (pinfunction "GND_2_G2") (pintype "bidirectional"))
      (node (ref "J4") (pin "G3") (pinfunction "GND_3_G3") (pintype "bidirectional"))
      (node (ref "J4") (pin "G4") (pinfunction "GND_4_G4") (pintype "bidirectional"))
      (node (ref "J4") (pin "P6") (pinfunction "VSS_P6") (pintype "bidirectional"))
      (node (ref "MCP73831") (pin "2") (pinfunction "VSS_2") (pintype "power_in"))
      (node (ref "R1_PWRUSB") (pin "1") (pinfunction "1_1") (pintype "passive"))
      (node (ref "R2") (pin "1") (pinfunction "1_1") (pintype "passive"))
      (node (ref "R2-USB") (pin "2") (pinfunction "2_2") (pintype "passive"))
      (node (ref "R2-USB1") (pin "1") (pinfunction "1_1") (pintype "passive"))
      (node (ref "R2_BAT") (pin "1") (pinfunction "1_1") (pintype "passive"))
      (node (ref "R4") (pin "2") (pinfunction "2_2") (pintype "passive"))
      (node (ref "RESET_BUTTON") (pin "1") (pinfunction "1_1") (pintype "passive"))
      (node (ref "RESET_BUTTON") (pin "2") (pinfunction "2_2") (pintype "passive"))
      (node (ref "SENSOR2") (pin "1") (pinfunction "GND_1") (pintype "power_in"))
      (node (ref "SENSOR2") (pin "5") (pinfunction "SDO_5") (pintype "bidirectional"))
      (node (ref "SENSOR2") (pin "7") (pinfunction "GND_7") (pintype "power_in"))
      (node (ref "SJ1") (pin "1") (pinfunction "1_1") (pintype "passive"))
      (node (ref "TP4") (pin "TP") (pinfunction "TP_TP") (pintype "input"))
      (node (ref "TP5") (pin "TP") (pinfunction "TP_TP") (pintype "input"))
      (node (ref "U1") (pin "4") (pinfunction "GND_4") (pintype "power_in"))
      (node (ref "U1") (pin "9") (pinfunction "EXP_9") (pintype "passive"))
      (node (ref "U2") (pin "1") (pinfunction "GND_1") (pintype "power_in"))
      (node (ref "U2") (pin "28") (pinfunction "GND_28") (pintype "power_in"))
      (node (ref "U2") (pin "29_1") (pinfunction "GND_29_1") (pintype "power_in"))
      (node (ref "U2") (pin "29_2") (pinfunction "GND_29_2") (pintype "power_in"))
      (node (ref "U2") (pin "29_3") (pinfunction "GND_29_3") (pintype "power_in"))
      (node (ref "U2") (pin "29_4") (pinfunction "GND_29_4") (pintype "power_in"))
      (node (ref "U2") (pin "29_5") (pinfunction "GND_29_5") (pintype "power_in"))
      (node (ref "U2") (pin "29_6") (pinfunction "GND_29_6") (pintype "power_in"))
      (node (ref "U2") (pin "29_7") (pinfunction "GND_29_7") (pintype "power_in"))
      (node (ref "U2") (pin "29_8") (pinfunction "GND_29_8") (pintype "power_in"))
      (node (ref "U2") (pin "29_9") (pinfunction "GND_29_9") (pintype "power_in"))
      (node (ref "U3") (pin "13") (pinfunction "GND_13") (pintype "power_in"))
      (node (ref "U4") (pin "1") (pinfunction "CTG_1") (pintype "power_in"))
      (node (ref "U4") (pin "4") (pinfunction "GND_4") (pintype "power_in"))
      (node (ref "U4") (pin "6") (pinfunction "QSTRT_6") (pintype "input"))
      (node (ref "U4") (pin "9") (pinfunction "EP_9") (pintype "power_in"))
    )
    (net (code "14") (name "GPIO18") (class "Default")
      (node (ref "R1") (pin "2") (pinfunction "2_2") (pintype "passive"))
      (node (ref "U2") (pin "10") (pinfunction "IO8_10") (pintype "bidirectional"))
    )
    (net (code "15") (name "I2C_PW") (class "Default")
      (node (ref "C1") (pin "1") (pinfunction "1_1") (pintype "passive"))
      (node (ref "C2") (pin "1") (pinfunction "1_1") (pintype "passive"))
      (node (ref "R1_PINH") (pin "2") (pinfunction "2_2") (pintype "passive"))
      (node (ref "R2-PINH") (pin "2") (pinfunction "2_2") (pintype "passive"))
      (node (ref "SENSOR2") (pin "2") (pinfunction "CSB_2") (pintype "input"))
      (node (ref "SENSOR2") (pin "6") (pinfunction "VDDIO_6") (pintype "power_in"))
      (node (ref "SENSOR2") (pin "8") (pinfunction "VDD_8") (pintype "power_in"))
      (node (ref "U2") (pin "17") (pinfunction "IO19_17") (pintype "bidirectional"))
    )
    (net (code "16") (name "INT_RTC") (class "Default")
      (node (ref "R1_PINH1") (pin "1") (pinfunction "1_1") (pintype "passive"))
      (node (ref "TP15") (pin "TP") (pinfunction "TP_TP") (pintype "input"))
      (node (ref "U2") (pin "8") (pinfunction "IO0_8") (pintype "bidirectional"))
      (node (ref "U3") (pin "3") (pinfunction "SQW/~{INT}_3") (pintype "output"))
    )
    (net (code "17") (name "IO{slash}BOOT") (class "Default")
      (node (ref "BOOT_BUTTON") (pin "3") (pinfunction "3_3") (pintype "passive"))
      (node (ref "BOOT_BUTTON") (pin "4") (pinfunction "4_4") (pintype "passive"))
      (node (ref "C6") (pin "1") (pinfunction "1_1") (pintype "passive"))
      (node (ref "R_BOOT") (pin "2") (pinfunction "2_2") (pintype "passive"))
      (node (ref "U2") (pin "15") (pinfunction "IO9_15") (pintype "bidirectional"))
    )
    (net (code "18") (name "IO{slash}CHANGE") (class "Default")
      (node (ref "C10") (pin "1") (pinfunction "1_1") (pintype "passive"))
      (node (ref "CHANGE_BUTTON") (pin "3") (pinfunction "3_3") (pintype "passive"))
      (node (ref "CHANGE_BUTTON") (pin "4") (pinfunction "4_4") (pintype "passive"))
      (node (ref "R_CHANGE") (pin "2") (pinfunction "2_2") (pintype "passive"))
      (node (ref "U2") (pin "23") (pinfunction "IO15_23") (pintype "bidirectional"))
    )
    (net (code "19") (name "MISO") (class "Default")
      (node (ref "D12") (pin "2") (pinfunction "2_2") (pintype "passive"))
      (node (ref "J4") (pin "P7") (pinfunction "DAT0_P7") (pintype "bidirectional"))
      (node (ref "R8") (pin "1") (pinfunction "1_1") (pintype "passive"))
      (node (ref "TP6") (pin "TP") (pinfunction "TP_TP") (pintype "input"))
      (node (ref "U1") (pin "2") (pinfunction "DO(IO1)_2") (pintype "bidirectional"))
      (node (ref "U2") (pin "27") (pinfunction "IO2_27") (pintype "bidirectional"))
    )
    (net (code "20") (name "MOSI") (class "Default")
      (node (ref "D11") (pin "2") (pinfunction "2_2") (pintype "passive"))
      (node (ref "J1") (pin "14") (pinfunction "14_14") (pintype "bidirectional"))
      (node (ref "J4") (pin "P3") (pinfunction "CMD_P3") (pintype "bidirectional"))
      (node (ref "R7") (pin "1") (pinfunction "1_1") (pintype "passive"))
      (node (ref "TP7") (pin "TP") (pinfunction "TP_TP") (pintype "input"))
      (node (ref "U1") (pin "5") (pinfunction "DI(IO0)_5") (pintype "bidirectional"))
      (node (ref "U2") (pin "7") (pinfunction "IO7_7") (pintype "bidirectional"))
    )
    (net (code "21") (name "Net-(CHG_LED-PadC)") (class "Default")
      (node (ref "CHG_LED") (pin "C") (pinfunction "C_C") (pintype "passive"))
      (node (ref "R1_BAT") (pin "1") (pinfunction "1_1") (pintype "passive"))
    )
    (net (code "22") (name "Net-(D2-CATHODE)") (class "Default")
      (node (ref "C1_BAT1") (pin "1") (pinfunction "1_1") (pintype "passive"))
      (node (ref "D2") (pin "1") (pinfunction "CATHODE_1") (pintype "bidirectional"))
      (node (ref "IC2") (pin "1") (pinfunction "VIN_1") (pintype "bidirectional"))
      (node (ref "IC2") (pin "3") (pinfunction "CE_3") (pintype "bidirectional"))
      (node (ref "Q3") (pin "2") (pinfunction "S_2") (pintype "bidirectional"))
    )
    (net (code "23") (name "Net-(D3-A)") (class "Default")
      (node (ref "C4") (pin "1") (pinfunction "1_1") (pintype "passive"))
      (node (ref "D3") (pin "2") (pinfunction "A_2") (pintype "bidirectional"))
      (node (ref "D4") (pin "1") (pinfunction "K_1") (pintype "bidirectional"))
    )
    (net (code "24") (name "Net-(D7-CATHODE)") (class "Default")
      (node (ref "D7") (pin "1") (pinfunction "CATHODE_1") (pintype "bidirectional"))
      (node (ref "R_CAPACITOR") (pin "2") (pinfunction "2_2") (pintype "passive"))
    )
    (net (code "25") (name "Net-(EPD_C1-Pad1)") (class "Default")
      (node (ref "EPD_C1") (pin "1") (pinfunction "1_1") (pintype "passive"))
      (node (ref "J1") (pin "4") (pinfunction "4_4") (pintype "bidirectional"))
    )
    (net (code "26") (name "Net-(EPD_C2-Pad1)") (class "Default")
      (node (ref "EPD_C2") (pin "1") (pinfunction "1_1") (pintype "passive"))
      (node (ref "J1") (pin "5") (pinfunction "5_5") (pintype "bidirectional"))
    )
    (net (code "27") (name "Net-(EPD_C6-Pad1)") (class "Default")
      (node (ref "EPD_C6") (pin "1") (pinfunction "1_1") (pintype "passive"))
      (node (ref "J1") (pin "18") (pinfunction "18_18") (pintype "bidirectional"))
    )
    (net (code "28") (name "Net-(EPD_C7-Pad1)") (class "Default")
      (node (ref "EPD_C7") (pin "1") (pinfunction "1_1") (pintype "passive"))
      (node (ref "J1") (pin "19") (pinfunction "19_19") (pintype "bidirectional"))
    )
    (net (code "29") (name "Net-(EPD_C8-Pad1)") (class "Default")
      (node (ref "EPD_C8") (pin "1") (pinfunction "1_1") (pintype "passive"))
      (node (ref "J1") (pin "20") (pinfunction "20_20") (pintype "bidirectional"))
    )
    (net (code "30") (name "Net-(EPD_C10-Pad1)") (class "Default")
      (node (ref "EPD_C10") (pin "1") (pinfunction "1_1") (pintype "passive"))
      (node (ref "J1") (pin "22") (pinfunction "22_22") (pintype "bidirectional"))
    )
    (net (code "31") (name "Net-(EPD_C12-Pad1)") (class "Default")
      (node (ref "EPD_C12") (pin "1") (pinfunction "1_1") (pintype "passive"))
      (node (ref "J1") (pin "24") (pinfunction "24_24") (pintype "bidirectional"))
    )
    (net (code "32") (name "Net-(IC1-CT)") (class "Default")
      (node (ref "C_DELAY") (pin "1") (pinfunction "1_1") (pintype "passive"))
      (node (ref "IC1") (pin "5") (pinfunction "CT_5") (pintype "bidirectional"))
    )
    (net (code "33") (name "Net-(J2-PadA5)") (class "Default")
      (node (ref "J2") (pin "A5") (pinfunction "A5_A5") (pintype "bidirectional"))
      (node (ref "R2-USB1") (pin "2") (pinfunction "2_2") (pintype "passive"))
    )
    (net (code "34") (name "Net-(J2-PadB5)") (class "Default")
      (node (ref "J2") (pin "B5") (pinfunction "B5_B5") (pintype "bidirectional"))
      (node (ref "R2-USB") (pin "1") (pinfunction "1_1") (pintype "passive"))
    )
    (net (code "35") (name "Net-(MCP73831-PROG)") (class "Default")
      (node (ref "MCP73831") (pin "5") (pinfunction "PROG_5") (pintype "input"))
      (node (ref "R2_BAT") (pin "2") (pinfunction "2_2") (pintype "passive"))
    )
    (net (code "36") (name "Net-(MCP73831-STAT)") (class "Default")
      (node (ref "MCP73831") (pin "1") (pinfunction "STAT_1") (pintype "output"))
      (node (ref "R1_BAT") (pin "2") (pinfunction "2_2") (pintype "passive"))
    )
    (net (code "37") (name "PREVGH") (class "Default")
      (node (ref "D5") (pin "1") (pinfunction "K_1") (pintype "bidirectional"))
      (node (ref "EPD_C9") (pin "1") (pinfunction "1_1") (pintype "passive"))
      (node (ref "J1") (pin "21") (pinfunction "21_21") (pintype "bidirectional"))
    )
    (net (code "38") (name "PREVGL") (class "Default")
      (node (ref "D4") (pin "2") (pinfunction "A_2") (pintype "bidirectional"))
      (node (ref "EPD_C11") (pin "1") (pinfunction "1_1") (pintype "passive"))
      (node (ref "J1") (pin "23") (pinfunction "23_23") (pintype "bidirectional"))
    )
    (net (code "39") (name "RESE") (class "Default")
      (node (ref "J1") (pin "3") (pinfunction "3_3") (pintype "bidirectional"))
      (node (ref "Q1") (pin "2") (pinfunction "S_2") (pintype "bidirectional"))
      (node (ref "R3") (pin "1") (pinfunction "1_1") (pintype "passive"))
    )
    (net (code "40") (name "RESE'") (class "Default")
      (node (ref "R2") (pin "2") (pinfunction "2_2") (pintype "passive"))
      (node (ref "R3") (pin "2") (pinfunction "2_2") (pintype "passive"))
      (node (ref "SJ1") (pin "2") (pinfunction "2_2") (pintype "passive"))
    )
    (net (code "41") (name "RESET") (class "Default")
      (node (ref "C5") (pin "1") (pinfunction "1_1") (pintype "passive"))
      (node (ref "IC1") (pin "1") (pinfunction "VOUT_1") (pintype "bidirectional"))
      (node (ref "RESET_BUTTON") (pin "3") (pinfunction "3_3") (pintype "passive"))
      (node (ref "RESET_BUTTON") (pin "4") (pinfunction "4_4") (pintype "passive"))
      (node (ref "R_RESET") (pin "2") (pinfunction "2_2") (pintype "passive"))
      (node (ref "U2") (pin "3") (pinfunction "EN_3") (pintype "input"))
    )
    (net (code "42") (name "RTC_RST") (class "Default")
      (node (ref "U2") (pin "16") (pinfunction "IO18_16") (pintype "bidirectional"))
      (node (ref "U3") (pin "4") (pinfunction "~{RST}_4") (pintype "input"))
    )
    (net (code "43") (name "RX") (class "Default")
      (node (ref "TP2") (pin "TP") (pinfunction "TP_TP") (pintype "input"))
      (node (ref "U2") (pin "24") (pinfunction "RXD0/GPIO17_24") (pintype "bidirectional"))
    )
    (net (code "44") (name "SCK") (class "Default")
      (node (ref "D10") (pin "2") (pinfunction "2_2") (pintype "passive"))
      (node (ref "J1") (pin "13") (pinfunction "13_13") (pintype "bidirectional"))
      (node (ref "J4") (pin "P5") (pinfunction "CLK_P5") (pintype "bidirectional"))
      (node (ref "R6") (pin "1") (pinfunction "1_1") (pintype "passive"))
      (node (ref "TP8") (pin "TP") (pinfunction "TP_TP") (pintype "input"))
      (node (ref "U1") (pin "6") (pinfunction "CLK_6") (pintype "input"))
      (node (ref "U2") (pin "6") (pinfunction "IO6_6") (pintype "bidirectional"))
    )
    (net (code "45") (name "SCL") (class "Default")
      (node (ref "J3") (pin "4") (pinfunction "4_4") (pintype "passive"))
      (node (ref "R2-PINH") (pin "1") (pinfunction "1_1") (pintype "passive"))
      (node (ref "SENSOR2") (pin "4") (pinfunction "SCK_4") (pintype "input"))
      (node (ref "U2") (pin "20") (pinfunction "IO22_20") (pintype "bidirectional"))
      (node (ref "U3") (pin "16") (pinfunction "SCL_16") (pintype "input"))
      (node (ref "U4") (pin "7") (pinfunction "SCL_7") (pintype "input"))
    )
    (net (code "46") (name "SDA") (class "Default")
      (node (ref "J3") (pin "3") (pinfunction "3_3") (pintype "passive"))
      (node (ref "R1_PINH") (pin "1") (pinfunction "1_1") (pintype "passive"))
      (node (ref "SENSOR2") (pin "3") (pinfunction "SDI_3") (pintype "bidirectional"))
      (node (ref "U2") (pin "19") (pinfunction "IO21_19") (pintype "bidirectional"))
      (node (ref "U3") (pin "15") (pinfunction "SDA_15") (pintype "bidirectional"))
      (node (ref "U4") (pin "8") (pinfunction "SDA_8") (pintype "bidirectional"))
    )
    (net (code "47") (name "SRC") (class "Default")
      (node (ref "C4") (pin "2") (pinfunction "2_2") (pintype "passive"))
      (node (ref "D5") (pin "2") (pinfunction "A_2") (pintype "bidirectional"))
      (node (ref "L1") (pin "1") (pinfunction "1_1") (pintype "passive"))
      (node (ref "Q1") (pin "3") (pinfunction "D_3") (pintype "bidirectional"))
    )
    (net (code "48") (name "SS_SD") (class "Default")
      (node (ref "D8") (pin "2") (pinfunction "2_2") (pintype "passive"))
      (node (ref "J4") (pin "P2") (pinfunction "CD/DAT3_P2") (pintype "bidirectional"))
      (node (ref "R10") (pin "1") (pinfunction "1_1") (pintype "passive"))
      (node (ref "U2") (pin "4") (pinfunction "IO4_4") (pintype "bidirectional"))
    )
    (net (code "49") (name "TX") (class "Default")
      (node (ref "TP1") (pin "TP") (pinfunction "TP_TP") (pintype "input"))
      (node (ref "U2") (pin "25") (pinfunction "TXD0/GPIO16_25") (pintype "bidirectional"))
    )
    (net (code "50") (name "USB_D+") (class "Default")
      (node (ref "D1") (pin "1") (pinfunction "I/O1_1_1") (pintype "bidirectional"))
      (node (ref "U2") (pin "14") (pinfunction "IO13_14") (pintype "bidirectional"))
    )
    (net (code "51") (name "USB_D-") (class "Default")
      (node (ref "D1") (pin "3") (pinfunction "I/O2_1_3") (pintype "bidirectional"))
      (node (ref "U2") (pin "13") (pinfunction "IO12_13") (pintype "bidirectional"))
    )
    (net (code "52") (name "VBAT") (class "Default")
      (node (ref "C2_BAT") (pin "1") (pinfunction "1_1") (pintype "passive"))
      (node (ref "MCP73831") (pin "3") (pinfunction "VBAT_3") (pintype "power_in"))
      (node (ref "Q3") (pin "3") (pinfunction "D_3") (pintype "bidirectional"))
      (node (ref "TP3") (pin "TP") (pinfunction "TP_TP") (pintype "input"))
      (node (ref "U4") (pin "2") (pinfunction "CELL_2") (pintype "power_in"))
      (node (ref "U4") (pin "3") (pinfunction "VDD_3") (pintype "power_in"))
    )
    (net (code "53") (name "VBUS") (class "Default")
      (node (ref "C1_BAT") (pin "1") (pinfunction "1_1") (pintype "passive"))
      (node (ref "C4_USB") (pin "1") (pinfunction "1_1") (pintype "passive"))
      (node (ref "C5_USB") (pin "1") (pinfunction "1_1") (pintype "passive"))
      (node (ref "CHG_LED") (pin "A") (pinfunction "A_A") (pintype "passive"))
      (node (ref "D1") (pin "5") (pinfunction "VBUS_5") (pintype "bidirectional"))
      (node (ref "D2") (pin "2") (pinfunction "ANODE_2") (pintype "bidirectional"))
      (node (ref "MCP73831") (pin "4") (pinfunction "VIN_4") (pintype "power_in"))
      (node (ref "PFMF.050.1") (pin "2") (pinfunction "2_2") (pintype "passive"))
      (node (ref "Q3") (pin "1") (pinfunction "G_1") (pintype "bidirectional"))
      (node (ref "R1_PWRUSB") (pin "2") (pinfunction "2_2") (pintype "passive"))
      (node (ref "TP14") (pin "TP") (pinfunction "TP_TP") (pintype "input"))
    )
    (net (code "54") (name "VRTC") (class "Default")
      (node (ref "C10_SUPERCAP") (pin "1") (pinfunction "1_1") (pintype "passive"))
      (node (ref "C8") (pin "1") (pinfunction "1_1") (pintype "passive"))
      (node (ref "R_CAPACITOR") (pin "1") (pinfunction "1_1") (pintype "passive"))
      (node (ref "U3") (pin "14") (pinfunction "VBAT_14") (pintype "power_in"))
    )
    (net (code "55") (name "VUSB") (class "Default")
      (node (ref "J2") (pin "A4") (pinfunction "A4_A4") (pintype "bidirectional"))
      (node (ref "J2") (pin "A9") (pinfunction "A9_A9") (pintype "bidirectional"))
      (node (ref "J2") (pin "B4") (pinfunction "B4_B4") (pintype "bidirectional"))
      (node (ref "J2") (pin "B9") (pinfunction "B9_B9") (pintype "bidirectional"))
      (node (ref "PFMF.050.1") (pin "1") (pinfunction "1_1") (pintype "passive"))
    )
    (net (code "56") (name "unconnected-(IC1-NC-Pad4)") (class "Default")
      (node (ref "IC1") (pin "4") (pinfunction "NC_4") (pintype "no_connect"))
    )
    (net (code "57") (name "unconnected-(IC2-NC-Pad4)") (class "Default")
      (node (ref "IC2") (pin "4") (pinfunction "NC_4") (pintype "no_connect"))
    )
    (net (code "58") (name "unconnected-(J1-Pad1)") (class "Default")
      (node (ref "J1") (pin "1") (pinfunction "1_1") (pintype "bidirectional"))
    )
    (net (code "59") (name "unconnected-(J1-Pad6)") (class "Default")
      (node (ref "J1") (pin "6") (pinfunction "6_6") (pintype "bidirectional"))
    )
    (net (code "60") (name "unconnected-(J1-Pad7)") (class "Default")
      (node (ref "J1") (pin "7") (pinfunction "7_7") (pintype "bidirectional"))
    )
    (net (code "61") (name "unconnected-(J2-PadA8)") (class "Default")
      (node (ref "J2") (pin "A8") (pinfunction "A8_A8") (pintype "bidirectional"))
    )
    (net (code "62") (name "unconnected-(J2-PadB8)") (class "Default")
      (node (ref "J2") (pin "B8") (pinfunction "B8_B8") (pintype "bidirectional"))
    )
    (net (code "63") (name "unconnected-(J4-DAT1-PadP8)") (class "Default")
      (node (ref "J4") (pin "P8") (pinfunction "DAT1_P8") (pintype "bidirectional"))
    )
    (net (code "64") (name "unconnected-(J4-DAT2-PadP1)") (class "Default")
      (node (ref "J4") (pin "P1") (pinfunction "DAT2_P1") (pintype "bidirectional"))
    )
    (net (code "65") (name "unconnected-(J4-DETECTION_1-PadS1)") (class "Default")
      (node (ref "J4") (pin "S1") (pinfunction "DETECTION_1_S1") (pintype "bidirectional"))
    )
    (net (code "66") (name "unconnected-(J4-DETECTION_2-PadS2)") (class "Default")
      (node (ref "J4") (pin "S2") (pinfunction "DETECTION_2_S2") (pintype "bidirectional"))
    )
    (net (code "67") (name "unconnected-(U2-NC-Pad22)") (class "Default")
      (node (ref "U2") (pin "22") (pinfunction "NC_22") (pintype "no_connect"))
    )
    (net (code "68") (name "unconnected-(U4-~{ALERT}-Pad5)") (class "Default")
      (node (ref "U4") (pin "5") (pinfunction "~{ALERT}_5") (pintype "output"))
    )
  )
)
